# BoostStage.net
KiCad netlist of a schematic drawn in Altium Designer
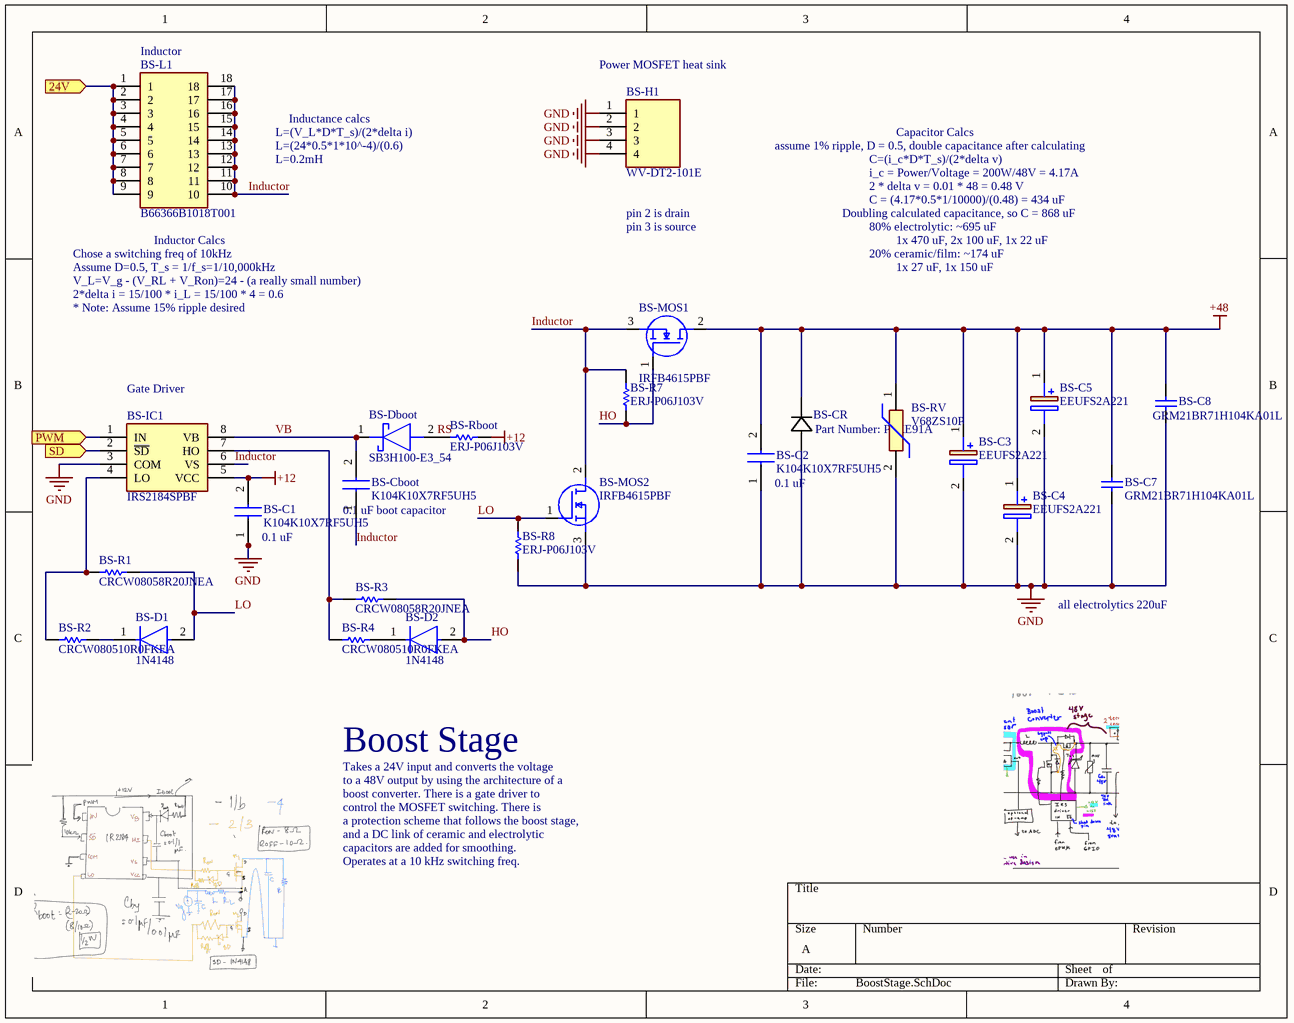
[diagram p0: BoostStage.SchDoc]

(export (version "E")
  (design (tool "Eeschema 10.0.6"))
  (components
    (comp (ref "BS-C1")
      (value "K104K10X7RF5UH5")
      (footprint "SamacSys:K104K10X7RF5UH5")
      (description "Capacitor")
      (fields (field (name "MOUSER PART NUMBER") "594-K104K10X7RF5UH5"))
      (libsource (lib "*") (part "K104K10X7RF5UH5"))
    )
    (comp (ref "BS-C2")
      (value "K104K10X7RF5UH5")
      (footprint "SamacSys:K104K10X7RF5UH5")
      (description "Capacitor")
      (fields (field (name "MOUSER PART NUMBER") "594-K104K10X7RF5UH5"))
      (libsource (lib "*") (part "K104K10X7RF5UH5"))
    )
    (comp (ref "BS-C3")
      (value "EEUFS2A221")
      (footprint "SamacSys:CAPPRD500W65D1250H2700")
      (description "Capacitor Polarised")
      (libsource (lib "*") (part "EEUFS2A221"))
    )
    (comp (ref "BS-C4")
      (value "EEUFS2A221")
      (footprint "SamacSys:CAPPRD500W65D1250H2700")
      (description "Capacitor Polarised")
      (libsource (lib "*") (part "EEUFS2A221"))
    )
    (comp (ref "BS-C5")
      (value "EEUFS2A221")
      (footprint "SamacSys:CAPPRD500W65D1250H2700")
      (description "Capacitor Polarised")
      (libsource (lib "*") (part "EEUFS2A221"))
    )
    (comp (ref "BS-C7")
      (value "GRM21BR71H104KA01L")
      (footprint "CAPC2013X135X45ML10T25")
      (description "Chip Capacitor, 0.1 uF, +/- 10%, 50 V, -55 to 125 degC, 0805 (2012 Metric), RoHS, Tape and Reel")
      (fields (field (name "VOLTAGE") "50V") (field (name "TOLERANCE") "10%"))
      (libsource (lib "Altium Content Vault") (part "CAP-NP-2"))
    )
    (comp (ref "BS-C8")
      (value "GRM21BR71H104KA01L")
      (footprint "CAPC2013X135X45ML10T25")
      (description "Chip Capacitor, 0.1 uF, +/- 10%, 50 V, -55 to 125 degC, 0805 (2012 Metric), RoHS, Tape and Reel")
      (fields (field (name "VOLTAGE") "50V") (field (name "TOLERANCE") "10%"))
      (libsource (lib "Altium Content Vault") (part "CAP-NP-2"))
    )
    (comp (ref "BS-Cboot")
      (value "K104K10X7RF5UH5")
      (footprint "SamacSys:K104K10X7RF5UH5")
      (description "Capacitor")
      (fields (field (name "MOUSER PART NUMBER") "594-K104K10X7RF5UH5"))
      (libsource (lib "*") (part "K104K10X7RF5UH5"))
    )
    (comp (ref "BS-CR")
      (value "Part Number: P6KE91A")
      (footprint "P6KESeries")
      (description "No Description Available")
      (fields
        (field (name "MANUFACTURER_PART_NUMBER") "P6KE91A")
        (field (name "COPYRIGHT") "Copyright (C) 2018 Accelerated Designs. All rights reserved")
      )
      (libsource (lib "ee_453_yourname") (part "P6KE91A"))
    )
    (comp (ref "BS-D1")
      (value "1N4148")
      (footprint "FP-017AG-MFG")
      (description "DIODE GEN PURP 100V 200MA DO35")
      (fields (field (name "VOLTAGE") "100V"))
      (libsource (lib "Altium Content Vault") (part "d7152d700b627762746794eb795d46e"))
    )
    (comp (ref "BS-D2")
      (value "1N4148")
      (footprint "FP-017AG-MFG")
      (description "DIODE GEN PURP 100V 200MA DO35")
      (fields (field (name "VOLTAGE") "100V"))
      (libsource (lib "Altium Content Vault") (part "d7152d700b627762746794eb795d46e"))
    )
    (comp (ref "BS-Dboot")
      (value "SB3H100-E3_54")
      (footprint "SamacSys:DIOAD2855W132L835D505")
      (description "Schottky Diode")
      (fields
        (field (name "MANUFACTURER_PART_NUMBER") "SB3H100-E3/54")
        (field (name "MOUSER PART NUMBER") "625-SB3H100-E3")
      )
      (libsource (lib "*") (part "SB3H100-E3_54"))
    )
    (comp (ref "BS-H1")
      (value "WV-DT2-101E")
      (footprint "SamacSys:WVDT2101E")
      (description "Power MOSFET heat sink")
      (fields (field (name "MOUSER PART NUMBER") "588-WV-DT2-101E"))
      (libsource (lib "*") (part "WV-DT2-101E"))
    )
    (comp (ref "BS-IC1")
      (value "IRS2184SPBF")
      (footprint "SamacSys:SOIC127P600X175-8N")
      (description "Integrated Circuit")
      (fields (field (name "MOUSER PART NUMBER") "942-IRS2184SPBF"))
      (libsource (lib "*") (part "IRS2184SPBF"))
    )
    (comp (ref "BS-L1")
      (value "B66366B1018T001")
      (footprint "SamacSys:B66366B1018T001")
      (description "Undefined or Miscellaneous")
      (libsource (lib "*") (part "B66366B1018T001"))
    )
    (comp (ref "BS-MOS1")
      (value "IRFB4615PBF")
      (footprint "SamacSys:TO254P483X1016X1994-3P")
      (description "MOSFET (N-Channel)")
      (fields (field (name "MOUSER PART NUMBER") "942-IRFB4615PBF"))
      (libsource (lib "*") (part "IRFB4615PBF"))
    )
    (comp (ref "BS-MOS2")
      (value "IRFB4615PBF")
      (footprint "SamacSys:TO254P483X1016X1994-3P")
      (description "MOSFET (N-Channel)")
      (fields (field (name "MOUSER PART NUMBER") "942-IRFB4615PBF"))
      (libsource (lib "*") (part "IRFB4615PBF"))
    )
    (comp (ref "BS-R1")
      (value "CRCW08058R20JNEA")
      (footprint "RESC2013X50X30NL20T20")
      (fields (field (name "MANUFACTURER") "Vishay Dale"))
      (libsource (lib "Altium Content Vault") (part "RES"))
    )
    (comp (ref "BS-R2")
      (value "CRCW080510R0FKEA")
      (footprint "RESC2013X50X30NL20T20")
      (fields (field (name "MANUFACTURER") "Vishay Dale"))
      (libsource (lib "Altium Content Vault") (part "RES"))
    )
    (comp (ref "BS-R3")
      (value "CRCW08058R20JNEA")
      (footprint "RESC2013X50X30NL20T20")
      (fields (field (name "MANUFACTURER") "Vishay Dale"))
      (libsource (lib "Altium Content Vault") (part "RES"))
    )
    (comp (ref "BS-R4")
      (value "CRCW080510R0FKEA")
      (footprint "RESC2013X50X30NL20T20")
      (fields (field (name "MANUFACTURER") "Vishay Dale"))
      (libsource (lib "Altium Content Vault") (part "RES"))
    )
    (comp (ref "BS-R7")
      (value "ERJ-P06J103V")
      (footprint "RESC2013X70X40ML20T20")
      (fields (field (name "MANUFACTURER") "Panasonic"))
      (libsource (lib "Altium Content Vault") (part "RES"))
    )
    (comp (ref "BS-R8")
      (value "ERJ-P06J103V")
      (footprint "RESC2013X70X40ML20T20")
      (fields (field (name "MANUFACTURER") "Panasonic"))
      (libsource (lib "Altium Content Vault") (part "RES"))
    )
    (comp (ref "BS-Rboot")
      (value "ERJ-P06J103V")
      (footprint "RESC2013X70X40ML20T20")
      (fields (field (name "MANUFACTURER") "Panasonic"))
      (libsource (lib "Altium Content Vault") (part "RES"))
    )
    (comp (ref "BS-RV")
      (value "V68ZS10P")
      (footprint "SamacSys:V68ZS10P")
      (description "Varistor")
      (fields (field (name "MOUSER PART NUMBER") "576-V68ZS10P"))
      (libsource (lib "*") (part "V68ZS10P"))
    )
  )
  (nets
    (net (code "1") (name "+12") (class "Default")
      (node (ref "BS-C1") (pin "2") (pinfunction "2_2") (pintype "passive"))
      (node (ref "BS-IC1") (pin "5") (pinfunction "VCC_5") (pintype "passive"))
      (node (ref "BS-Rboot") (pin "2") (pinfunction "2_2") (pintype "passive"))
    )
    (net (code "2") (name "+48") (class "Default")
      (node (ref "BS-C2") (pin "2") (pinfunction "2_2") (pintype "passive"))
      (node (ref "BS-C3") (pin "1") (pinfunction "+_1") (pintype "passive"))
      (node (ref "BS-C4") (pin "1") (pinfunction "+_1") (pintype "passive"))
      (node (ref "BS-C5") (pin "1") (pinfunction "+_1") (pintype "passive"))
      (node (ref "BS-C7") (pin "2") (pinfunction "2_2") (pintype "passive"))
      (node (ref "BS-C8") (pin "2") (pinfunction "2_2") (pintype "passive"))
      (node (ref "BS-CR") (pin "1") (pinfunction "1_1") (pintype "passive"))
      (node (ref "BS-MOS1") (pin "2") (pinfunction "D_2") (pintype "passive"))
      (node (ref "BS-RV") (pin "1") (pinfunction "1_1") (pintype "passive"))
    )
    (net (code "3") (name "/24V") (class "Default")
      (node (ref "BS-L1") (pin "1") (pinfunction "1_1") (pintype "passive"))
      (node (ref "BS-L1") (pin "2") (pinfunction "2_2") (pintype "passive"))
      (node (ref "BS-L1") (pin "3") (pinfunction "3_3") (pintype "passive"))
      (node (ref "BS-L1") (pin "4") (pinfunction "4_4") (pintype "passive"))
      (node (ref "BS-L1") (pin "5") (pinfunction "5_5") (pintype "passive"))
      (node (ref "BS-L1") (pin "6") (pinfunction "6_6") (pintype "passive"))
      (node (ref "BS-L1") (pin "7") (pinfunction "7_7") (pintype "passive"))
      (node (ref "BS-L1") (pin "8") (pinfunction "8_8") (pintype "passive"))
      (node (ref "BS-L1") (pin "9") (pinfunction "9_9") (pintype "passive"))
    )
    (net (code "4") (name "/HO") (class "Default")
      (node (ref "BS-D2") (pin "2") (pinfunction "A_2") (pintype "passive"))
      (node (ref "BS-MOS1") (pin "1") (pinfunction "G_1") (pintype "passive"))
      (node (ref "BS-R3") (pin "2") (pinfunction "2_2") (pintype "passive"))
      (node (ref "BS-R7") (pin "1") (pinfunction "1_1") (pintype "passive"))
    )
    (net (code "5") (name "/Inductor") (class "Default")
      (node (ref "BS-Cboot") (pin "1") (pinfunction "1_1") (pintype "passive"))
      (node (ref "BS-IC1") (pin "6") (pinfunction "VS_6") (pintype "passive"))
      (node (ref "BS-L1") (pin "10") (pinfunction "10_10") (pintype "passive"))
      (node (ref "BS-L1") (pin "11") (pinfunction "11_11") (pintype "passive"))
      (node (ref "BS-L1") (pin "12") (pinfunction "12_12") (pintype "passive"))
      (node (ref "BS-L1") (pin "13") (pinfunction "13_13") (pintype "passive"))
      (node (ref "BS-L1") (pin "14") (pinfunction "14_14") (pintype "passive"))
      (node (ref "BS-L1") (pin "15") (pinfunction "15_15") (pintype "passive"))
      (node (ref "BS-L1") (pin "16") (pinfunction "16_16") (pintype "passive"))
      (node (ref "BS-L1") (pin "17") (pinfunction "17_17") (pintype "passive"))
      (node (ref "BS-L1") (pin "18") (pinfunction "18_18") (pintype "passive"))
      (node (ref "BS-MOS1") (pin "3") (pinfunction "S_3") (pintype "passive"))
      (node (ref "BS-MOS2") (pin "2") (pinfunction "D_2") (pintype "passive"))
      (node (ref "BS-R7") (pin "2") (pinfunction "2_2") (pintype "passive"))
    )
    (net (code "6") (name "/LO") (class "Default")
      (node (ref "BS-D1") (pin "2") (pinfunction "A_2") (pintype "passive"))
      (node (ref "BS-MOS2") (pin "1") (pinfunction "G_1") (pintype "passive"))
      (node (ref "BS-R1") (pin "2") (pinfunction "2_2") (pintype "passive"))
      (node (ref "BS-R8") (pin "2") (pinfunction "2_2") (pintype "passive"))
    )
    (net (code "7") (name "/PWM") (class "Default")
      (node (ref "BS-IC1") (pin "1") (pinfunction "IN_1") (pintype "passive"))
    )
    (net (code "8") (name "/RS") (class "Default")
      (node (ref "BS-Dboot") (pin "2") (pinfunction "A_2") (pintype "passive"))
      (node (ref "BS-Rboot") (pin "1") (pinfunction "1_1") (pintype "passive"))
    )
    (net (code "9") (name "/SD") (class "Default")
      (node (ref "BS-IC1") (pin "2") (pinfunction "~{SD}_2") (pintype "passive"))
    )
    (net (code "10") (name "/VB") (class "Default")
      (node (ref "BS-Cboot") (pin "2") (pinfunction "2_2") (pintype "passive"))
      (node (ref "BS-Dboot") (pin "1") (pinfunction "K_1") (pintype "passive"))
      (node (ref "BS-IC1") (pin "8") (pinfunction "VB_8") (pintype "passive"))
    )
    (net (code "11") (name "GND") (class "Default")
      (node (ref "BS-C1") (pin "1") (pinfunction "1_1") (pintype "passive"))
      (node (ref "BS-C2") (pin "1") (pinfunction "1_1") (pintype "passive"))
      (node (ref "BS-C3") (pin "2") (pinfunction "-_2") (pintype "passive"))
      (node (ref "BS-C4") (pin "2") (pinfunction "-_2") (pintype "passive"))
      (node (ref "BS-C5") (pin "2") (pinfunction "-_2") (pintype "passive"))
      (node (ref "BS-C7") (pin "1") (pinfunction "1_1") (pintype "passive"))
      (node (ref "BS-C8") (pin "1") (pinfunction "1_1") (pintype "passive"))
      (node (ref "BS-CR") (pin "2") (pinfunction "2_2") (pintype "passive"))
      (node (ref "BS-H1") (pin "1") (pinfunction "1_1") (pintype "passive"))
      (node (ref "BS-H1") (pin "2") (pinfunction "2_2") (pintype "passive"))
      (node (ref "BS-H1") (pin "3") (pinfunction "3_3") (pintype "passive"))
      (node (ref "BS-H1") (pin "4") (pinfunction "4_4") (pintype "passive"))
      (node (ref "BS-IC1") (pin "3") (pinfunction "COM_3") (pintype "passive"))
      (node (ref "BS-MOS2") (pin "3") (pinfunction "S_3") (pintype "passive"))
      (node (ref "BS-R8") (pin "1") (pinfunction "1_1") (pintype "passive"))
      (node (ref "BS-RV") (pin "2") (pinfunction "2_2") (pintype "passive"))
    )
    (net (code "12") (name "Net-(BS-D1-C)") (class "Default")
      (node (ref "BS-D1") (pin "1") (pinfunction "C_1") (pintype "passive"))
      (node (ref "BS-R2") (pin "2") (pinfunction "2_2") (pintype "passive"))
    )
    (net (code "13") (name "Net-(BS-D2-C)") (class "Default")
      (node (ref "BS-D2") (pin "1") (pinfunction "C_1") (pintype "passive"))
      (node (ref "BS-R4") (pin "2") (pinfunction "2_2") (pintype "passive"))
    )
    (net (code "14") (name "Net-(BS-IC1-HO)") (class "Default")
      (node (ref "BS-IC1") (pin "7") (pinfunction "HO_7") (pintype "passive"))
      (node (ref "BS-R3") (pin "1") (pinfunction "1_1") (pintype "passive"))
      (node (ref "BS-R4") (pin "1") (pinfunction "1_1") (pintype "passive"))
    )
    (net (code "15") (name "Net-(BS-IC1-LO)") (class "Default")
      (node (ref "BS-IC1") (pin "4") (pinfunction "LO_4") (pintype "passive"))
      (node (ref "BS-R1") (pin "1") (pinfunction "1_1") (pintype "passive"))
      (node (ref "BS-R2") (pin "1") (pinfunction "1_1") (pintype "passive"))
    )
  )
)
